# Schematic.net
KiCad netlist of a schematic drawn in Altium Designer
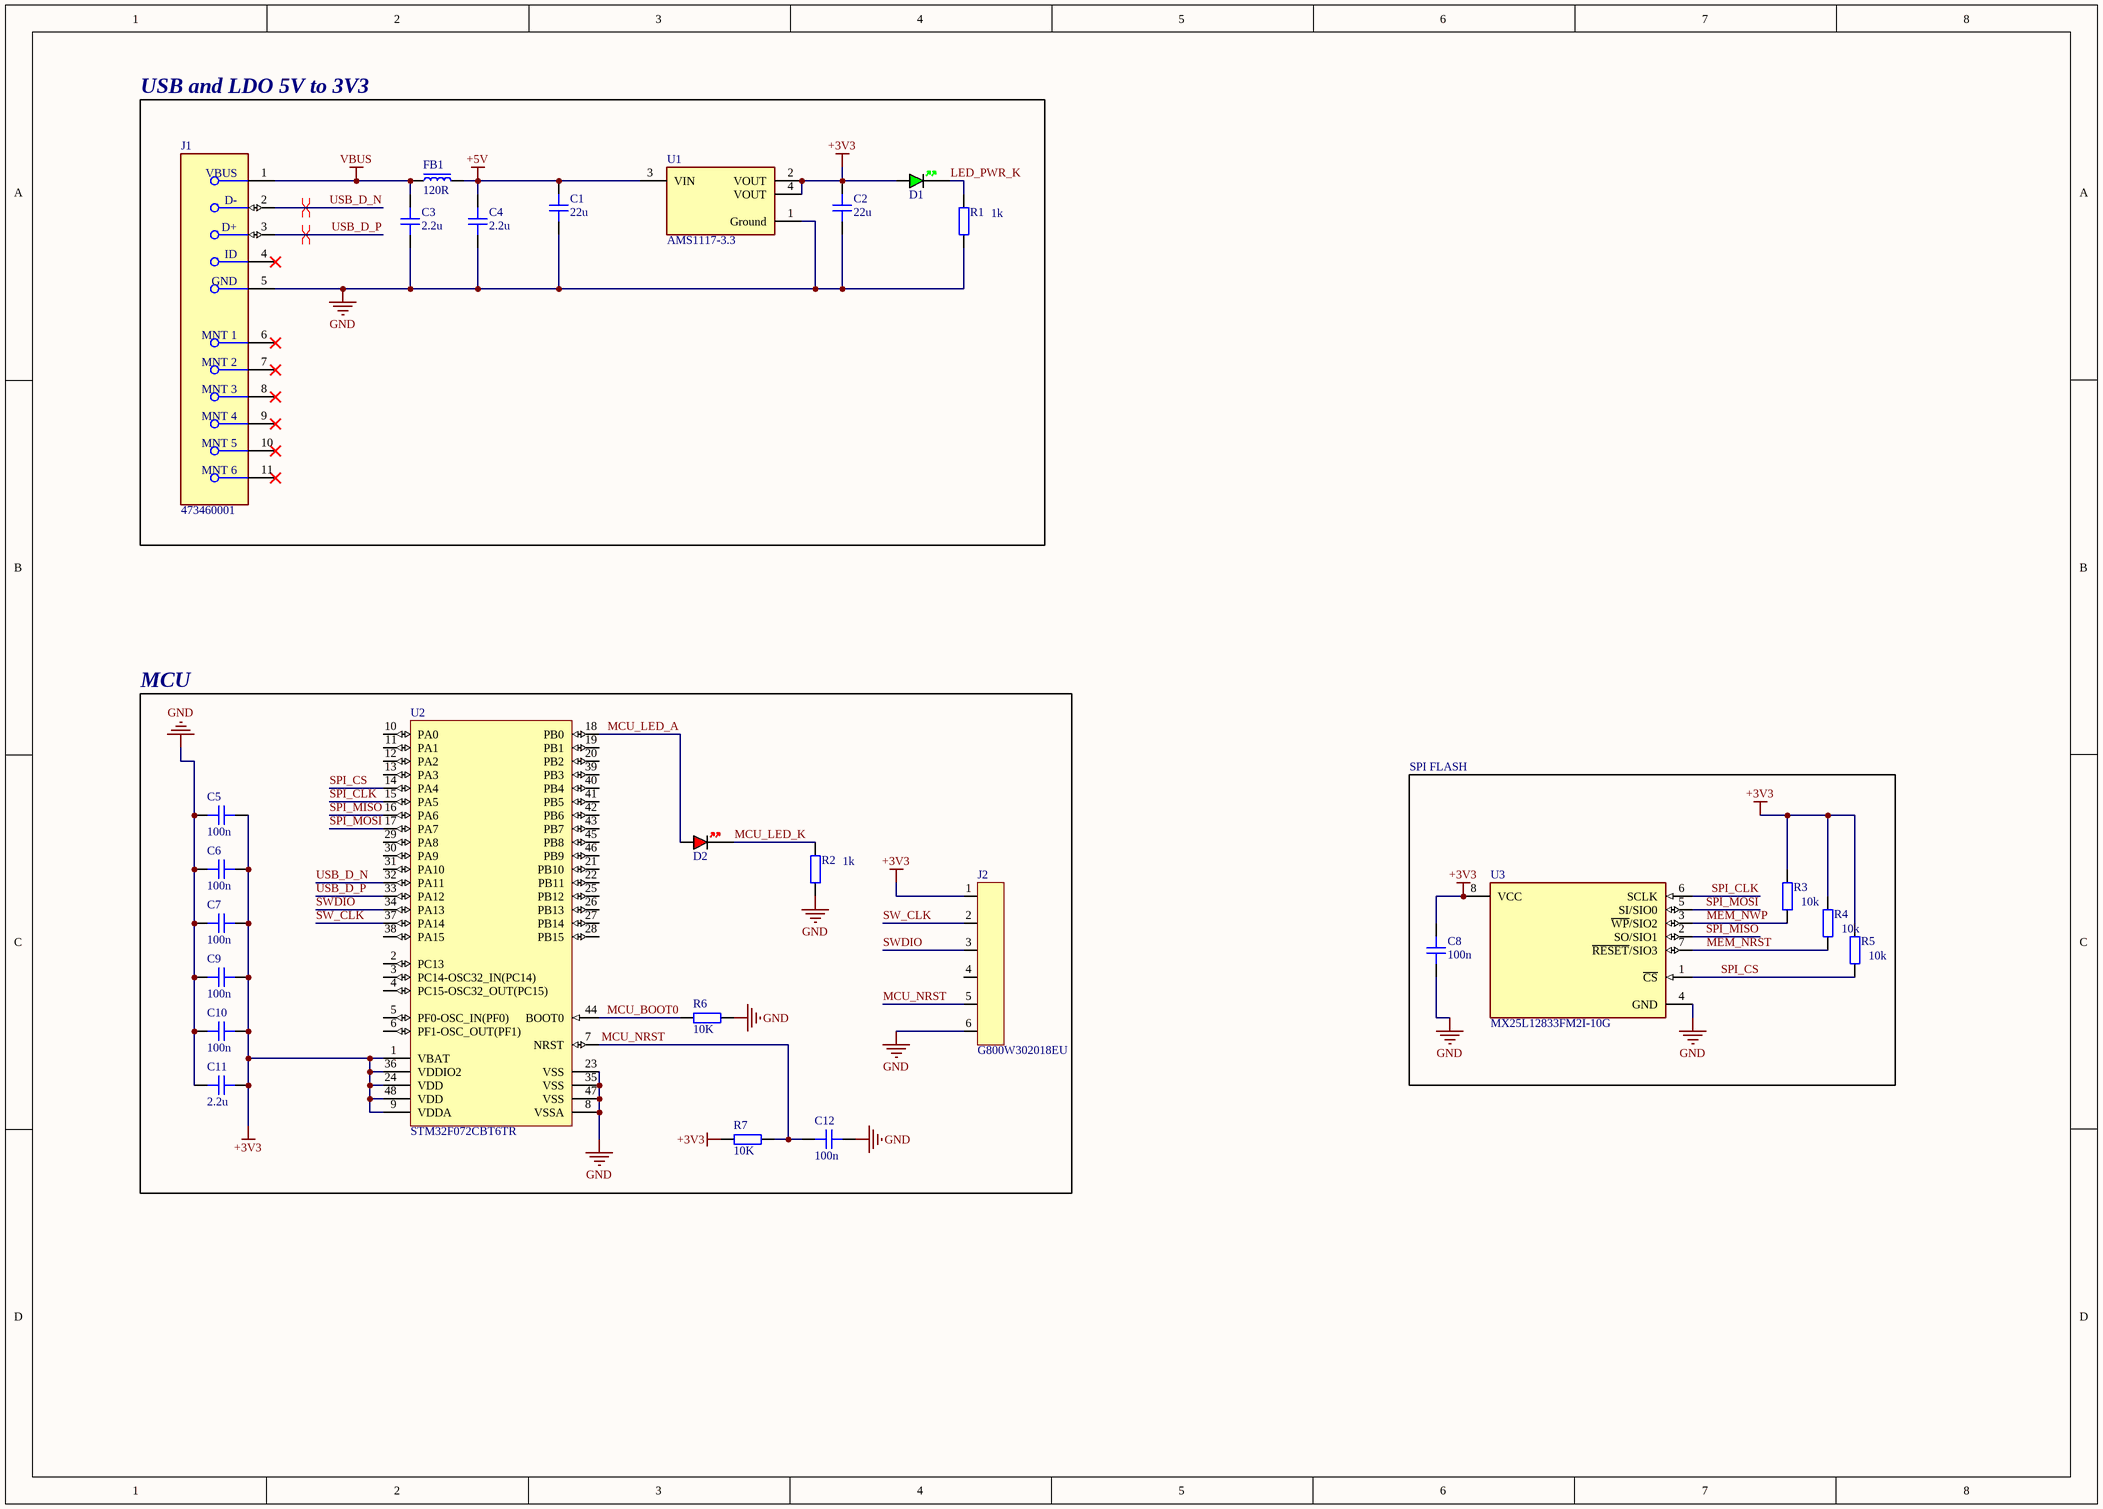
[diagram p0: Schematic.SchDoc]

(export (version "E")
  (design (tool "Eeschema 10.0.6"))
  (components
    (comp (ref "C1")
      (value "22u")
      (footprint "CAP_0805")
      (description "Capacitor SMD 0805")
      (libsource (lib "Schematic-Lib-PhilsLab") (part "CAP_0805"))
    )
    (comp (ref "C2")
      (value "22u")
      (footprint "CAP_0805")
      (description "Capacitor SMD 0805")
      (libsource (lib "Schematic-Lib-PhilsLab") (part "CAP_0805"))
    )
    (comp (ref "C3")
      (value "2.2u")
      (footprint "CAP_0603")
      (description "Capacitor SMD 0603")
      (libsource (lib "Schematic-Lib-PhilsLab") (part "CAP_0603"))
    )
    (comp (ref "C4")
      (value "2.2u")
      (footprint "CAP_0603")
      (description "Capacitor SMD 0603")
      (libsource (lib "Schematic-Lib-PhilsLab") (part "CAP_0603"))
    )
    (comp (ref "C5")
      (value "100n")
      (footprint "CAP_0402")
      (description "Capacitor SMD 0402")
      (libsource (lib "Schematic-Lib-PhilsLab") (part "CAP_0402"))
    )
    (comp (ref "C6")
      (value "100n")
      (footprint "CAP_0402")
      (description "Capacitor SMD 0402")
      (libsource (lib "Schematic-Lib-PhilsLab") (part "CAP_0402"))
    )
    (comp (ref "C7")
      (value "100n")
      (footprint "CAP_0402")
      (description "Capacitor SMD 0402")
      (libsource (lib "Schematic-Lib-PhilsLab") (part "CAP_0402"))
    )
    (comp (ref "C8")
      (value "100n")
      (footprint "CAP_0402")
      (description "Capacitor SMD 0402")
      (libsource (lib "Schematic-Lib-PhilsLab") (part "CAP_0402"))
    )
    (comp (ref "C9")
      (value "100n")
      (footprint "CAP_0402")
      (description "Capacitor SMD 0402")
      (libsource (lib "Schematic-Lib-PhilsLab") (part "CAP_0402"))
    )
    (comp (ref "C10")
      (value "100n")
      (footprint "CAP_0402")
      (description "Capacitor SMD 0402")
      (libsource (lib "Schematic-Lib-PhilsLab") (part "CAP_0402"))
    )
    (comp (ref "C11")
      (value "2.2u")
      (footprint "CAP_0603")
      (description "Capacitor SMD 0603")
      (libsource (lib "Schematic-Lib-PhilsLab") (part "CAP_0603"))
    )
    (comp (ref "C12")
      (value "100n")
      (footprint "CAP_0402")
      (description "Capacitor SMD 0402")
      (libsource (lib "Schematic-Lib-PhilsLab") (part "CAP_0402"))
    )
    (comp (ref "D1")
      (value "GREEN")
      (footprint "LED_0402_GREEN")
      (description "LED 0402 GREEN SMD")
      (libsource (lib "Schematic-Lib-PhilsLab") (part "LED_0402_GREEN"))
    )
    (comp (ref "D2")
      (value "RED")
      (footprint "LED_0402_RED")
      (description "LED 0402 RED SMD")
      (libsource (lib "Schematic-Lib-PhilsLab") (part "LED_0402_RED"))
    )
    (comp (ref "FB1")
      (value "120R")
      (footprint "FB_0603")
      (description "Ferrite Bead SMD 0603")
      (libsource (lib "Schematic-Lib-PhilsLab") (part "FB_0603"))
    )
    (comp (ref "J1")
      (value "473460001")
      (footprint "FP-473460001-MFG")
      (description "CONN RCPT USB2.0 MICRO B SMD R/A")
      (fields
        (field (name "OCTOPART") "https://octopart.com/47346-0001-molex-7164928")
        (field (name "MANUFACTURER") "Molex")
      )
      (libsource (lib "Altium Content Vault") (part "53ae1f1d9b557310b43ca686e5bb76a"))
    )
    (comp (ref "J2")
      (value "G800W302018EU")
      (footprint "G800W302018EU")
      (description "Pin Header 6 Position 2.54mm Pitch")
      (fields (field (name "MANUFACTURER") "Amphenol"))
      (libsource (lib "Schematic-Lib-PhilsLab") (part "G800W302018EU"))
    )
    (comp (ref "R1")
      (value "1k")
      (footprint "RES_0402")
      (description "Resistor SMD 0402")
      (libsource (lib "Schematic-Lib-PhilsLab") (part "RES_0402"))
    )
    (comp (ref "R2")
      (value "1k")
      (footprint "RES_0402")
      (description "Resistor SMD 0402")
      (libsource (lib "Schematic-Lib-PhilsLab") (part "RES_0402"))
    )
    (comp (ref "R3")
      (value "10k")
      (footprint "RES_0402")
      (description "Resistor SMD 0402")
      (libsource (lib "Schematic-Lib-PhilsLab") (part "RES_0402"))
    )
    (comp (ref "R4")
      (value "10k")
      (footprint "RES_0402")
      (description "Resistor SMD 0402")
      (libsource (lib "Schematic-Lib-PhilsLab") (part "RES_0402"))
    )
    (comp (ref "R5")
      (value "10k")
      (footprint "RES_0402")
      (description "Resistor SMD 0402")
      (libsource (lib "Schematic-Lib-PhilsLab") (part "RES_0402"))
    )
    (comp (ref "R6")
      (value "10K")
      (footprint "RES_0402")
      (description "Resistor SMD 0402")
      (libsource (lib "Schematic-Lib-PhilsLab") (part "RES_0402"))
    )
    (comp (ref "R7")
      (value "10K")
      (footprint "RES_0402")
      (description "Resistor SMD 0402")
      (libsource (lib "Schematic-Lib-PhilsLab") (part "RES_0402"))
    )
    (comp (ref "U1")
      (value "AMS1117-3.3")
      (footprint "FP-AMS1117-IPC_C")
      (description "LDO Voltage Regulators 1A, 3.3V")
      (fields
        (field (name "OCTOPART") "https://octopart.com/ams1117-3.3-advanced+monolithic+systems-25899300")
        (field (name "MANUFACTURER") "Advanced Monolithic Systems")
      )
      (libsource (lib "Altium Content Vault") (part "8bdbb5f8e77002000e30dd2845d0354"))
    )
    (comp (ref "U2")
      (value "STM32F072CBT6TR")
      (footprint "STM-LQFP48_M")
      (libsource (lib "Altium Content Vault") (part "MC-ARM-STM32F07X-LQFP48"))
    )
    (comp (ref "U3")
      (value "MX25L12833FM2I-10G")
      (footprint "FP-MX25L12833FM2I-10G-MFG")
      (description "IC FLASH 128MBIT SPI/QUAD 8SOP")
      (libsource (lib "Altium Content Vault") (part "3d93ad905be0c27c551c1345014b9ea"))
    )
  )
  (nets
    (net (code "1") (name "+3V3") (class "Default")
      (node (ref "C10") (pin "2") (pinfunction "2_2") (pintype "passive"))
      (node (ref "C11") (pin "1") (pinfunction "1_1") (pintype "passive"))
      (node (ref "C2") (pin "2") (pinfunction "2_2") (pintype "passive"))
      (node (ref "C5") (pin "2") (pinfunction "2_2") (pintype "passive"))
      (node (ref "C6") (pin "2") (pinfunction "2_2") (pintype "passive"))
      (node (ref "C7") (pin "2") (pinfunction "2_2") (pintype "passive"))
      (node (ref "C8") (pin "2") (pinfunction "2_2") (pintype "passive"))
      (node (ref "C9") (pin "2") (pinfunction "2_2") (pintype "passive"))
      (node (ref "D1") (pin "A") (pinfunction "A_A") (pintype "passive"))
      (node (ref "J2") (pin "1") (pinfunction "1_1") (pintype "passive"))
      (node (ref "R3") (pin "2") (pinfunction "2_2") (pintype "passive"))
      (node (ref "R4") (pin "2") (pinfunction "2_2") (pintype "passive"))
      (node (ref "R5") (pin "2") (pinfunction "2_2") (pintype "passive"))
      (node (ref "R7") (pin "2") (pinfunction "2_2") (pintype "passive"))
      (node (ref "U1") (pin "2") (pinfunction "VOUT_2") (pintype "passive"))
      (node (ref "U1") (pin "4") (pinfunction "VOUT_4") (pintype "passive"))
      (node (ref "U2") (pin "1") (pinfunction "VBAT_1") (pintype "power_in"))
      (node (ref "U2") (pin "24") (pinfunction "VDD_24") (pintype "power_in"))
      (node (ref "U2") (pin "36") (pinfunction "VDDIO2_36") (pintype "power_in"))
      (node (ref "U2") (pin "48") (pinfunction "VDD_48") (pintype "power_in"))
      (node (ref "U2") (pin "9") (pinfunction "VDDA_9") (pintype "power_in"))
      (node (ref "U3") (pin "8") (pinfunction "VCC_8") (pintype "power_in"))
    )
    (net (code "2") (name "+5V") (class "Default")
      (node (ref "C1") (pin "2") (pinfunction "2_2") (pintype "passive"))
      (node (ref "C4") (pin "2") (pinfunction "2_2") (pintype "passive"))
      (node (ref "FB1") (pin "2") (pinfunction "2_2") (pintype "passive"))
      (node (ref "U1") (pin "3") (pinfunction "VIN_3") (pintype "power_in"))
    )
    (net (code "3") (name "/LED_PWR_K") (class "Default")
      (node (ref "D1") (pin "K") (pinfunction "K_K") (pintype "passive"))
      (node (ref "R1") (pin "2") (pinfunction "2_2") (pintype "passive"))
    )
    (net (code "4") (name "/MCU_BOOT0") (class "Default")
      (node (ref "R6") (pin "2") (pinfunction "2_2") (pintype "passive"))
      (node (ref "U2") (pin "44") (pinfunction "BOOT0_44") (pintype "input"))
    )
    (net (code "5") (name "/MCU_LED_A") (class "Default")
      (node (ref "D2") (pin "A") (pinfunction "A_A") (pintype "passive"))
      (node (ref "U2") (pin "18") (pinfunction "PB0_18") (pintype "bidirectional"))
    )
    (net (code "6") (name "/MCU_LED_K") (class "Default")
      (node (ref "D2") (pin "K") (pinfunction "K_K") (pintype "passive"))
      (node (ref "R2") (pin "2") (pinfunction "2_2") (pintype "passive"))
    )
    (net (code "7") (name "/MCU_NRST") (class "Default")
      (node (ref "C12") (pin "1") (pinfunction "1_1") (pintype "passive"))
      (node (ref "J2") (pin "5") (pinfunction "5_5") (pintype "passive"))
      (node (ref "R7") (pin "1") (pinfunction "1_1") (pintype "passive"))
      (node (ref "U2") (pin "7") (pinfunction "NRST_7") (pintype "bidirectional"))
    )
    (net (code "8") (name "/MEM_NRST") (class "Default")
      (node (ref "R4") (pin "1") (pinfunction "1_1") (pintype "passive"))
      (node (ref "U3") (pin "7") (pinfunction "~{RESET}/SIO3_7") (pintype "bidirectional"))
    )
    (net (code "9") (name "/MEM_NWP") (class "Default")
      (node (ref "R3") (pin "1") (pinfunction "1_1") (pintype "passive"))
      (node (ref "U3") (pin "3") (pinfunction "~{WP}/SIO2_3") (pintype "bidirectional"))
    )
    (net (code "10") (name "/SPI_CLK") (class "Default")
      (node (ref "U2") (pin "15") (pinfunction "PA5_15") (pintype "bidirectional"))
      (node (ref "U3") (pin "6") (pinfunction "SCLK_6") (pintype "input"))
    )
    (net (code "11") (name "/SPI_CS") (class "Default")
      (node (ref "R5") (pin "1") (pinfunction "1_1") (pintype "passive"))
      (node (ref "U2") (pin "14") (pinfunction "PA4_14") (pintype "bidirectional"))
      (node (ref "U3") (pin "1") (pinfunction "~{CS}_1") (pintype "input"))
    )
    (net (code "12") (name "/SPI_MISO") (class "Default")
      (node (ref "U2") (pin "16") (pinfunction "PA6_16") (pintype "bidirectional"))
      (node (ref "U3") (pin "2") (pinfunction "SO/SIO1_2") (pintype "bidirectional"))
    )
    (net (code "13") (name "/SPI_MOSI") (class "Default")
      (node (ref "U2") (pin "17") (pinfunction "PA7_17") (pintype "bidirectional"))
      (node (ref "U3") (pin "5") (pinfunction "SI/SIO0_5") (pintype "bidirectional"))
    )
    (net (code "14") (name "/SWDIO") (class "Default")
      (node (ref "J2") (pin "3") (pinfunction "3_3") (pintype "passive"))
      (node (ref "U2") (pin "34") (pinfunction "PA13_34") (pintype "bidirectional"))
    )
    (net (code "15") (name "/SW_CLK") (class "Default")
      (node (ref "J2") (pin "2") (pinfunction "2_2") (pintype "passive"))
      (node (ref "U2") (pin "37") (pinfunction "PA14_37") (pintype "bidirectional"))
    )
    (net (code "16") (name "/USB_D_N") (class "Default")
      (node (ref "J1") (pin "2") (pinfunction "D-_2") (pintype "bidirectional"))
      (node (ref "U2") (pin "32") (pinfunction "PA11_32") (pintype "bidirectional"))
    )
    (net (code "17") (name "/USB_D_P") (class "Default")
      (node (ref "J1") (pin "3") (pinfunction "D+_3") (pintype "bidirectional"))
      (node (ref "U2") (pin "33") (pinfunction "PA12_33") (pintype "bidirectional"))
    )
    (net (code "18") (name "GND") (class "Default")
      (node (ref "C1") (pin "1") (pinfunction "1_1") (pintype "passive"))
      (node (ref "C10") (pin "1") (pinfunction "1_1") (pintype "passive"))
      (node (ref "C11") (pin "2") (pinfunction "2_2") (pintype "passive"))
      (node (ref "C12") (pin "2") (pinfunction "2_2") (pintype "passive"))
      (node (ref "C2") (pin "1") (pinfunction "1_1") (pintype "passive"))
      (node (ref "C3") (pin "1") (pinfunction "1_1") (pintype "passive"))
      (node (ref "C4") (pin "1") (pinfunction "1_1") (pintype "passive"))
      (node (ref "C5") (pin "1") (pinfunction "1_1") (pintype "passive"))
      (node (ref "C6") (pin "1") (pinfunction "1_1") (pintype "passive"))
      (node (ref "C7") (pin "1") (pinfunction "1_1") (pintype "passive"))
      (node (ref "C8") (pin "1") (pinfunction "1_1") (pintype "passive"))
      (node (ref "C9") (pin "1") (pinfunction "1_1") (pintype "passive"))
      (node (ref "J1") (pin "5") (pinfunction "GND_5") (pintype "power_in"))
      (node (ref "J2") (pin "6") (pinfunction "6_6") (pintype "passive"))
      (node (ref "R1") (pin "1") (pinfunction "1_1") (pintype "passive"))
      (node (ref "R2") (pin "1") (pinfunction "1_1") (pintype "passive"))
      (node (ref "R6") (pin "1") (pinfunction "1_1") (pintype "passive"))
      (node (ref "U1") (pin "1") (pinfunction "Ground_1") (pintype "power_in"))
      (node (ref "U2") (pin "23") (pinfunction "VSS_23") (pintype "power_in"))
      (node (ref "U2") (pin "35") (pinfunction "VSS_35") (pintype "power_in"))
      (node (ref "U2") (pin "47") (pinfunction "VSS_47") (pintype "power_in"))
      (node (ref "U2") (pin "8") (pinfunction "VSSA_8") (pintype "power_in"))
      (node (ref "U3") (pin "4") (pinfunction "GND_4") (pintype "power_in"))
    )
    (net (code "19") (name "VBUS") (class "Default")
      (node (ref "C3") (pin "2") (pinfunction "2_2") (pintype "passive"))
      (node (ref "FB1") (pin "1") (pinfunction "1_1") (pintype "passive"))
      (node (ref "J1") (pin "1") (pinfunction "VBUS_1") (pintype "power_in"))
    )
    (net (code "20") (name "unconnected-(J1-ID-Pad4)") (class "Default")
      (node (ref "J1") (pin "4") (pinfunction "ID_4") (pintype "passive+no_connect"))
    )
    (net (code "21") (name "unconnected-(J1-MNT_1-Pad6)") (class "Default")
      (node (ref "J1") (pin "6") (pinfunction "MNT_1_6") (pintype "passive+no_connect"))
    )
    (net (code "22") (name "unconnected-(J1-MNT_2-Pad7)") (class "Default")
      (node (ref "J1") (pin "7") (pinfunction "MNT_2_7") (pintype "passive+no_connect"))
    )
    (net (code "23") (name "unconnected-(J1-MNT_3-Pad8)") (class "Default")
      (node (ref "J1") (pin "8") (pinfunction "MNT_3_8") (pintype "passive+no_connect"))
    )
    (net (code "24") (name "unconnected-(J1-MNT_4-Pad9)") (class "Default")
      (node (ref "J1") (pin "9") (pinfunction "MNT_4_9") (pintype "passive+no_connect"))
    )
    (net (code "25") (name "unconnected-(J1-MNT_5-Pad10)") (class "Default")
      (node (ref "J1") (pin "10") (pinfunction "MNT_5_10") (pintype "passive+no_connect"))
    )
    (net (code "26") (name "unconnected-(J1-MNT_6-Pad11)") (class "Default")
      (node (ref "J1") (pin "11") (pinfunction "MNT_6_11") (pintype "passive+no_connect"))
    )
    (net (code "27") (name "unconnected-(J2-Pad4)") (class "Default")
      (node (ref "J2") (pin "4") (pinfunction "4_4") (pintype "passive"))
    )
    (net (code "28") (name "unconnected-(U2-PA0-Pad10)") (class "Default")
      (node (ref "U2") (pin "10") (pinfunction "PA0_10") (pintype "bidirectional"))
    )
    (net (code "29") (name "unconnected-(U2-PA1-Pad11)") (class "Default")
      (node (ref "U2") (pin "11") (pinfunction "PA1_11") (pintype "bidirectional"))
    )
    (net (code "30") (name "unconnected-(U2-PA2-Pad12)") (class "Default")
      (node (ref "U2") (pin "12") (pinfunction "PA2_12") (pintype "bidirectional"))
    )
    (net (code "31") (name "unconnected-(U2-PA3-Pad13)") (class "Default")
      (node (ref "U2") (pin "13") (pinfunction "PA3_13") (pintype "bidirectional"))
    )
    (net (code "32") (name "unconnected-(U2-PA8-Pad29)") (class "Default")
      (node (ref "U2") (pin "29") (pinfunction "PA8_29") (pintype "bidirectional"))
    )
    (net (code "33") (name "unconnected-(U2-PA9-Pad30)") (class "Default")
      (node (ref "U2") (pin "30") (pinfunction "PA9_30") (pintype "bidirectional"))
    )
    (net (code "34") (name "unconnected-(U2-PA10-Pad31)") (class "Default")
      (node (ref "U2") (pin "31") (pinfunction "PA10_31") (pintype "bidirectional"))
    )
    (net (code "35") (name "unconnected-(U2-PA15-Pad38)") (class "Default")
      (node (ref "U2") (pin "38") (pinfunction "PA15_38") (pintype "bidirectional"))
    )
    (net (code "36") (name "unconnected-(U2-PB1-Pad19)") (class "Default")
      (node (ref "U2") (pin "19") (pinfunction "PB1_19") (pintype "bidirectional"))
    )
    (net (code "37") (name "unconnected-(U2-PB2-Pad20)") (class "Default")
      (node (ref "U2") (pin "20") (pinfunction "PB2_20") (pintype "bidirectional"))
    )
    (net (code "38") (name "unconnected-(U2-PB3-Pad39)") (class "Default")
      (node (ref "U2") (pin "39") (pinfunction "PB3_39") (pintype "bidirectional"))
    )
    (net (code "39") (name "unconnected-(U2-PB4-Pad40)") (class "Default")
      (node (ref "U2") (pin "40") (pinfunction "PB4_40") (pintype "bidirectional"))
    )
    (net (code "40") (name "unconnected-(U2-PB5-Pad41)") (class "Default")
      (node (ref "U2") (pin "41") (pinfunction "PB5_41") (pintype "bidirectional"))
    )
    (net (code "41") (name "unconnected-(U2-PB6-Pad42)") (class "Default")
      (node (ref "U2") (pin "42") (pinfunction "PB6_42") (pintype "bidirectional"))
    )
    (net (code "42") (name "unconnected-(U2-PB7-Pad43)") (class "Default")
      (node (ref "U2") (pin "43") (pinfunction "PB7_43") (pintype "bidirectional"))
    )
    (net (code "43") (name "unconnected-(U2-PB8-Pad45)") (class "Default")
      (node (ref "U2") (pin "45") (pinfunction "PB8_45") (pintype "bidirectional"))
    )
    (net (code "44") (name "unconnected-(U2-PB9-Pad46)") (class "Default")
      (node (ref "U2") (pin "46") (pinfunction "PB9_46") (pintype "bidirectional"))
    )
    (net (code "45") (name "unconnected-(U2-PB10-Pad21)") (class "Default")
      (node (ref "U2") (pin "21") (pinfunction "PB10_21") (pintype "bidirectional"))
    )
    (net (code "46") (name "unconnected-(U2-PB11-Pad22)") (class "Default")
      (node (ref "U2") (pin "22") (pinfunction "PB11_22") (pintype "bidirectional"))
    )
    (net (code "47") (name "unconnected-(U2-PB12-Pad25)") (class "Default")
      (node (ref "U2") (pin "25") (pinfunction "PB12_25") (pintype "bidirectional"))
    )
    (net (code "48") (name "unconnected-(U2-PB13-Pad26)") (class "Default")
      (node (ref "U2") (pin "26") (pinfunction "PB13_26") (pintype "bidirectional"))
    )
    (net (code "49") (name "unconnected-(U2-PB14-Pad27)") (class "Default")
      (node (ref "U2") (pin "27") (pinfunction "PB14_27") (pintype "bidirectional"))
    )
    (net (code "50") (name "unconnected-(U2-PB15-Pad28)") (class "Default")
      (node (ref "U2") (pin "28") (pinfunction "PB15_28") (pintype "bidirectional"))
    )
    (net (code "51") (name "unconnected-(U2-PC13-Pad2)") (class "Default")
      (node (ref "U2") (pin "2") (pinfunction "PC13_2") (pintype "bidirectional"))
    )
    (net (code "52") (name "unconnected-(U2-PC14-OSC32_IN(PC14)-Pad3)") (class "Default")
      (node (ref "U2") (pin "3") (pinfunction "PC14-OSC32_IN(PC14)_3") (pintype "bidirectional"))
    )
    (net (code "53") (name "unconnected-(U2-PC15-OSC32_OUT(PC15)-Pad4)") (class "Default")
      (node (ref "U2") (pin "4") (pinfunction "PC15-OSC32_OUT(PC15)_4") (pintype "bidirectional"))
    )
    (net (code "54") (name "unconnected-(U2-PF0-OSC_IN(PF0)-Pad5)") (class "Default")
      (node (ref "U2") (pin "5") (pinfunction "PF0-OSC_IN(PF0)_5") (pintype "bidirectional"))
    )
    (net (code "55") (name "unconnected-(U2-PF1-OSC_OUT(PF1)-Pad6)") (class "Default")
      (node (ref "U2") (pin "6") (pinfunction "PF1-OSC_OUT(PF1)_6") (pintype "bidirectional"))
    )
  )
)
